# base_station_power_supply.net
KiCad netlist of a schematic drawn in EAGLE
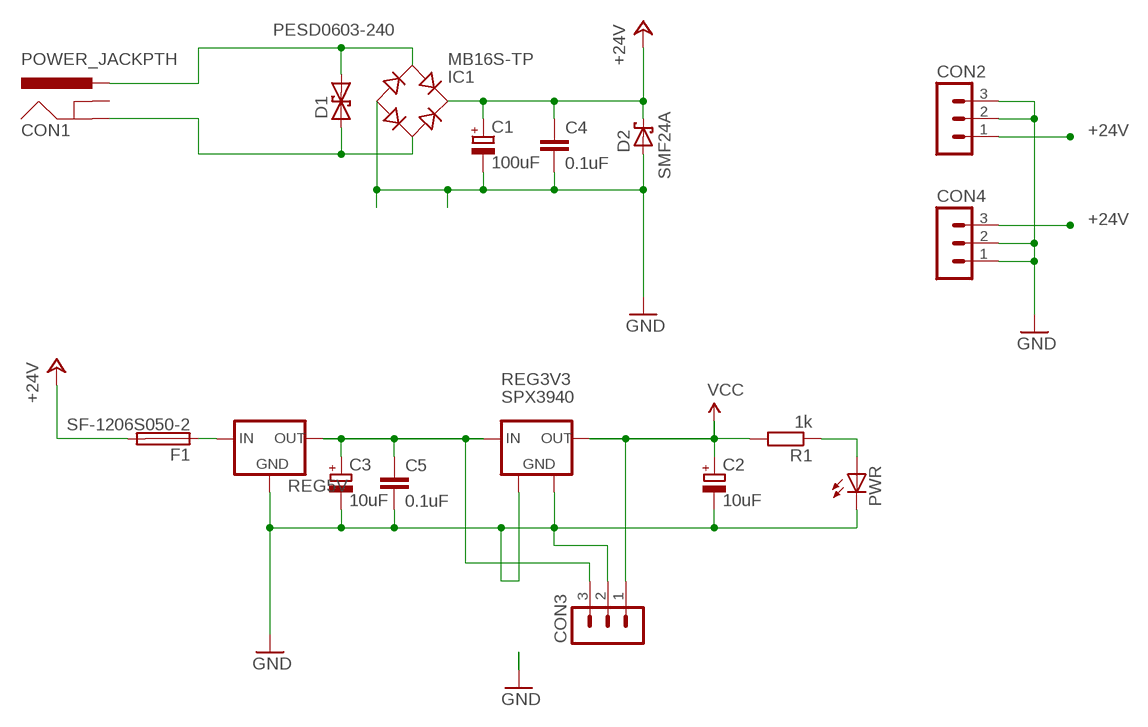
[diagram p0: schematic, sheet 1]

(export (version "E")
  (design (tool "Eeschema 10.0.6"))
  (components
    (comp (ref "C1")
      (value "100uF")
      (footprint "eagle-import:E5-10,5")
      (libsource (lib "eagle-import") (part "CPOL-EUE5-10.5"))
    )
    (comp (ref "C2")
      (value "10uF")
      (footprint "eagle-import:E2-5")
      (libsource (lib "eagle-import") (part "CPOL-EUE2-5"))
    )
    (comp (ref "C3")
      (value "10uF")
      (footprint "eagle-import:E5-10,5")
      (libsource (lib "eagle-import") (part "CPOL-EUE5-10.5"))
    )
    (comp (ref "C4")
      (value "0.1uF")
      (footprint "eagle-import:C0805")
      (libsource (lib "eagle-import") (part "C-EUC0805"))
    )
    (comp (ref "C5")
      (value "0.1uF")
      (footprint "eagle-import:C0805")
      (libsource (lib "eagle-import") (part "C-EUC0805"))
    )
    (comp (ref "CON1")
      (value "POWER_JACKPTH")
      (footprint "eagle-import:POWER_JACK_PTH")
      (libsource (lib "eagle-import") (part "POWER_JACKPTH"))
    )
    (comp (ref "CON2")
      (value "MA03-1")
      (footprint "eagle-import:MA03-1")
      (libsource (lib "eagle-import") (part "MA03-1"))
    )
    (comp (ref "CON3")
      (value "MA03-1")
      (footprint "eagle-import:MA03-1")
      (libsource (lib "eagle-import") (part "MA03-1"))
    )
    (comp (ref "CON4")
      (value "MA03-1")
      (footprint "eagle-import:MA03-1")
      (libsource (lib "eagle-import") (part "MA03-1"))
    )
    (comp (ref "D1")
      (value "PESD0603-240")
      (footprint "eagle-import:D0603")
      (libsource (lib "eagle-import") (part "PESD0603-240"))
    )
    (comp (ref "D2")
      (value "SMF24A")
      (footprint "eagle-import:SOD123")
      (libsource (lib "eagle-import") (part "SMF24A"))
    )
    (comp (ref "F1")
      (value "SF-1206S050-2")
      (footprint "eagle-import:F1206")
      (libsource (lib "eagle-import") (part "SF-1206S050-2"))
    )
    (comp (ref "IC1")
      (value "MB16S-TP")
      (footprint "eagle-import:SOIC-4")
      (libsource (lib "eagle-import") (part "MB16S-TP"))
    )
    (comp (ref "PWR")
      (value "LEDCHIPLED_0805")
      (footprint "eagle-import:CHIPLED_0805")
      (libsource (lib "eagle-import") (part "LEDCHIPLED_0805"))
    )
    (comp (ref "R1")
      (value "1k")
      (footprint "eagle-import:R0603")
      (libsource (lib "eagle-import") (part "R-EU_R0603"))
    )
    (comp (ref "REG3V3")
      (value "SPX3940")
      (footprint "eagle-import:SOT223")
      (libsource (lib "eagle-import") (part "SPX3940"))
    )
    (comp (ref "REG5V")
      (value "V_REG_OKI-78SRSINK")
      (footprint "eagle-import:TO220-IGO")
      (libsource (lib "eagle-import") (part "V_REG_OKI-78SRSINK"))
    )
  )
  (nets
    (net (code "1") (name "+24V") (class "Default")
      (node (ref "C1") (pin "+") (pinfunction "+_+") (pintype "passive"))
      (node (ref "C4") (pin "1") (pinfunction "1_1") (pintype "passive"))
      (node (ref "CON2") (pin "1") (pinfunction "1_1") (pintype "passive"))
      (node (ref "CON4") (pin "3") (pinfunction "3_3") (pintype "passive"))
      (node (ref "D2") (pin "C") (pinfunction "C_C") (pintype "passive"))
      (node (ref "F1") (pin "2") (pinfunction "2_2") (pintype "passive"))
      (node (ref "IC1") (pin "+") (pinfunction "+_+") (pintype "passive"))
    )
    (net (code "2") (name "GND") (class "Default")
      (node (ref "C1") (pin "-") (pinfunction "-_-") (pintype "passive"))
      (node (ref "C2") (pin "-") (pinfunction "-_-") (pintype "passive"))
      (node (ref "C3") (pin "-") (pinfunction "-_-") (pintype "passive"))
      (node (ref "C4") (pin "2") (pinfunction "2_2") (pintype "passive"))
      (node (ref "C5") (pin "2") (pinfunction "2_2") (pintype "passive"))
      (node (ref "CON2") (pin "2") (pinfunction "2_2") (pintype "passive"))
      (node (ref "CON2") (pin "3") (pinfunction "3_3") (pintype "passive"))
      (node (ref "CON3") (pin "2") (pinfunction "2_2") (pintype "passive"))
      (node (ref "CON4") (pin "1") (pinfunction "1_1") (pintype "passive"))
      (node (ref "CON4") (pin "2") (pinfunction "2_2") (pintype "passive"))
      (node (ref "D2") (pin "A") (pinfunction "A_A") (pintype "passive"))
      (node (ref "IC1") (pin "-") (pinfunction "-_-") (pintype "passive"))
      (node (ref "PWR") (pin "C") (pinfunction "C_C") (pintype "passive"))
      (node (ref "REG3V3") (pin "2") (pinfunction "GND_2") (pintype "power_in"))
      (node (ref "REG3V3") (pin "4") (pinfunction "GND_4") (pintype "power_in"))
      (node (ref "REG5V") (pin "GND") (pinfunction "GND_GND") (pintype "input"))
    )
    (net (code "3") (name "Net-(F1-Pad1)") (class "Default")
      (node (ref "F1") (pin "1") (pinfunction "1_1") (pintype "passive"))
      (node (ref "REG5V") (pin "IN") (pinfunction "IN_IN") (pintype "input"))
    )
    (net (code "4") (name "Net-(IC1-AC1)") (class "Default")
      (node (ref "CON1") (pin "PWR") (pinfunction "PWR_PWR") (pintype "bidirectional"))
      (node (ref "D1") (pin "2") (pinfunction "2_2") (pintype "passive"))
      (node (ref "IC1") (pin "~1") (pinfunction "AC1_~1") (pintype "passive"))
    )
    (net (code "5") (name "Net-(IC1-AC2)") (class "Default")
      (node (ref "CON1") (pin "GND") (pinfunction "GND_GND") (pintype "bidirectional"))
      (node (ref "D1") (pin "1") (pinfunction "1_1") (pintype "passive"))
      (node (ref "IC1") (pin "~2") (pinfunction "AC2_~2") (pintype "passive"))
    )
    (net (code "6") (name "Net-(PWR-PadA)") (class "Default")
      (node (ref "PWR") (pin "A") (pinfunction "A_A") (pintype "passive"))
      (node (ref "R1") (pin "1") (pinfunction "1_1") (pintype "passive"))
    )
    (net (code "7") (name "Net-(REG3V3-IN)") (class "Default")
      (node (ref "C3") (pin "+") (pinfunction "+_+") (pintype "passive"))
      (node (ref "C5") (pin "1") (pinfunction "1_1") (pintype "passive"))
      (node (ref "CON3") (pin "3") (pinfunction "3_3") (pintype "passive"))
      (node (ref "REG3V3") (pin "1") (pinfunction "IN_1") (pintype "power_in"))
      (node (ref "REG5V") (pin "OUT") (pinfunction "OUT_OUT") (pintype "output"))
    )
    (net (code "8") (name "VCC") (class "Default")
      (node (ref "C2") (pin "+") (pinfunction "+_+") (pintype "passive"))
      (node (ref "CON3") (pin "1") (pinfunction "1_1") (pintype "passive"))
      (node (ref "R1") (pin "2") (pinfunction "2_2") (pintype "passive"))
      (node (ref "REG3V3") (pin "3") (pinfunction "OUT_3") (pintype "power_in"))
    )
    (net (code "9") (name "unconnected-(CON1-PadGNDBREAK)") (class "Default")
      (node (ref "CON1") (pin "GNDBREAK") (pinfunction "GNDBREAK_GNDBREAK") (pintype "bidirectional"))
    )
  )
)
